# 1-Schematic_TT2.net
KiCad netlist of a schematic drawn in EasyEDA
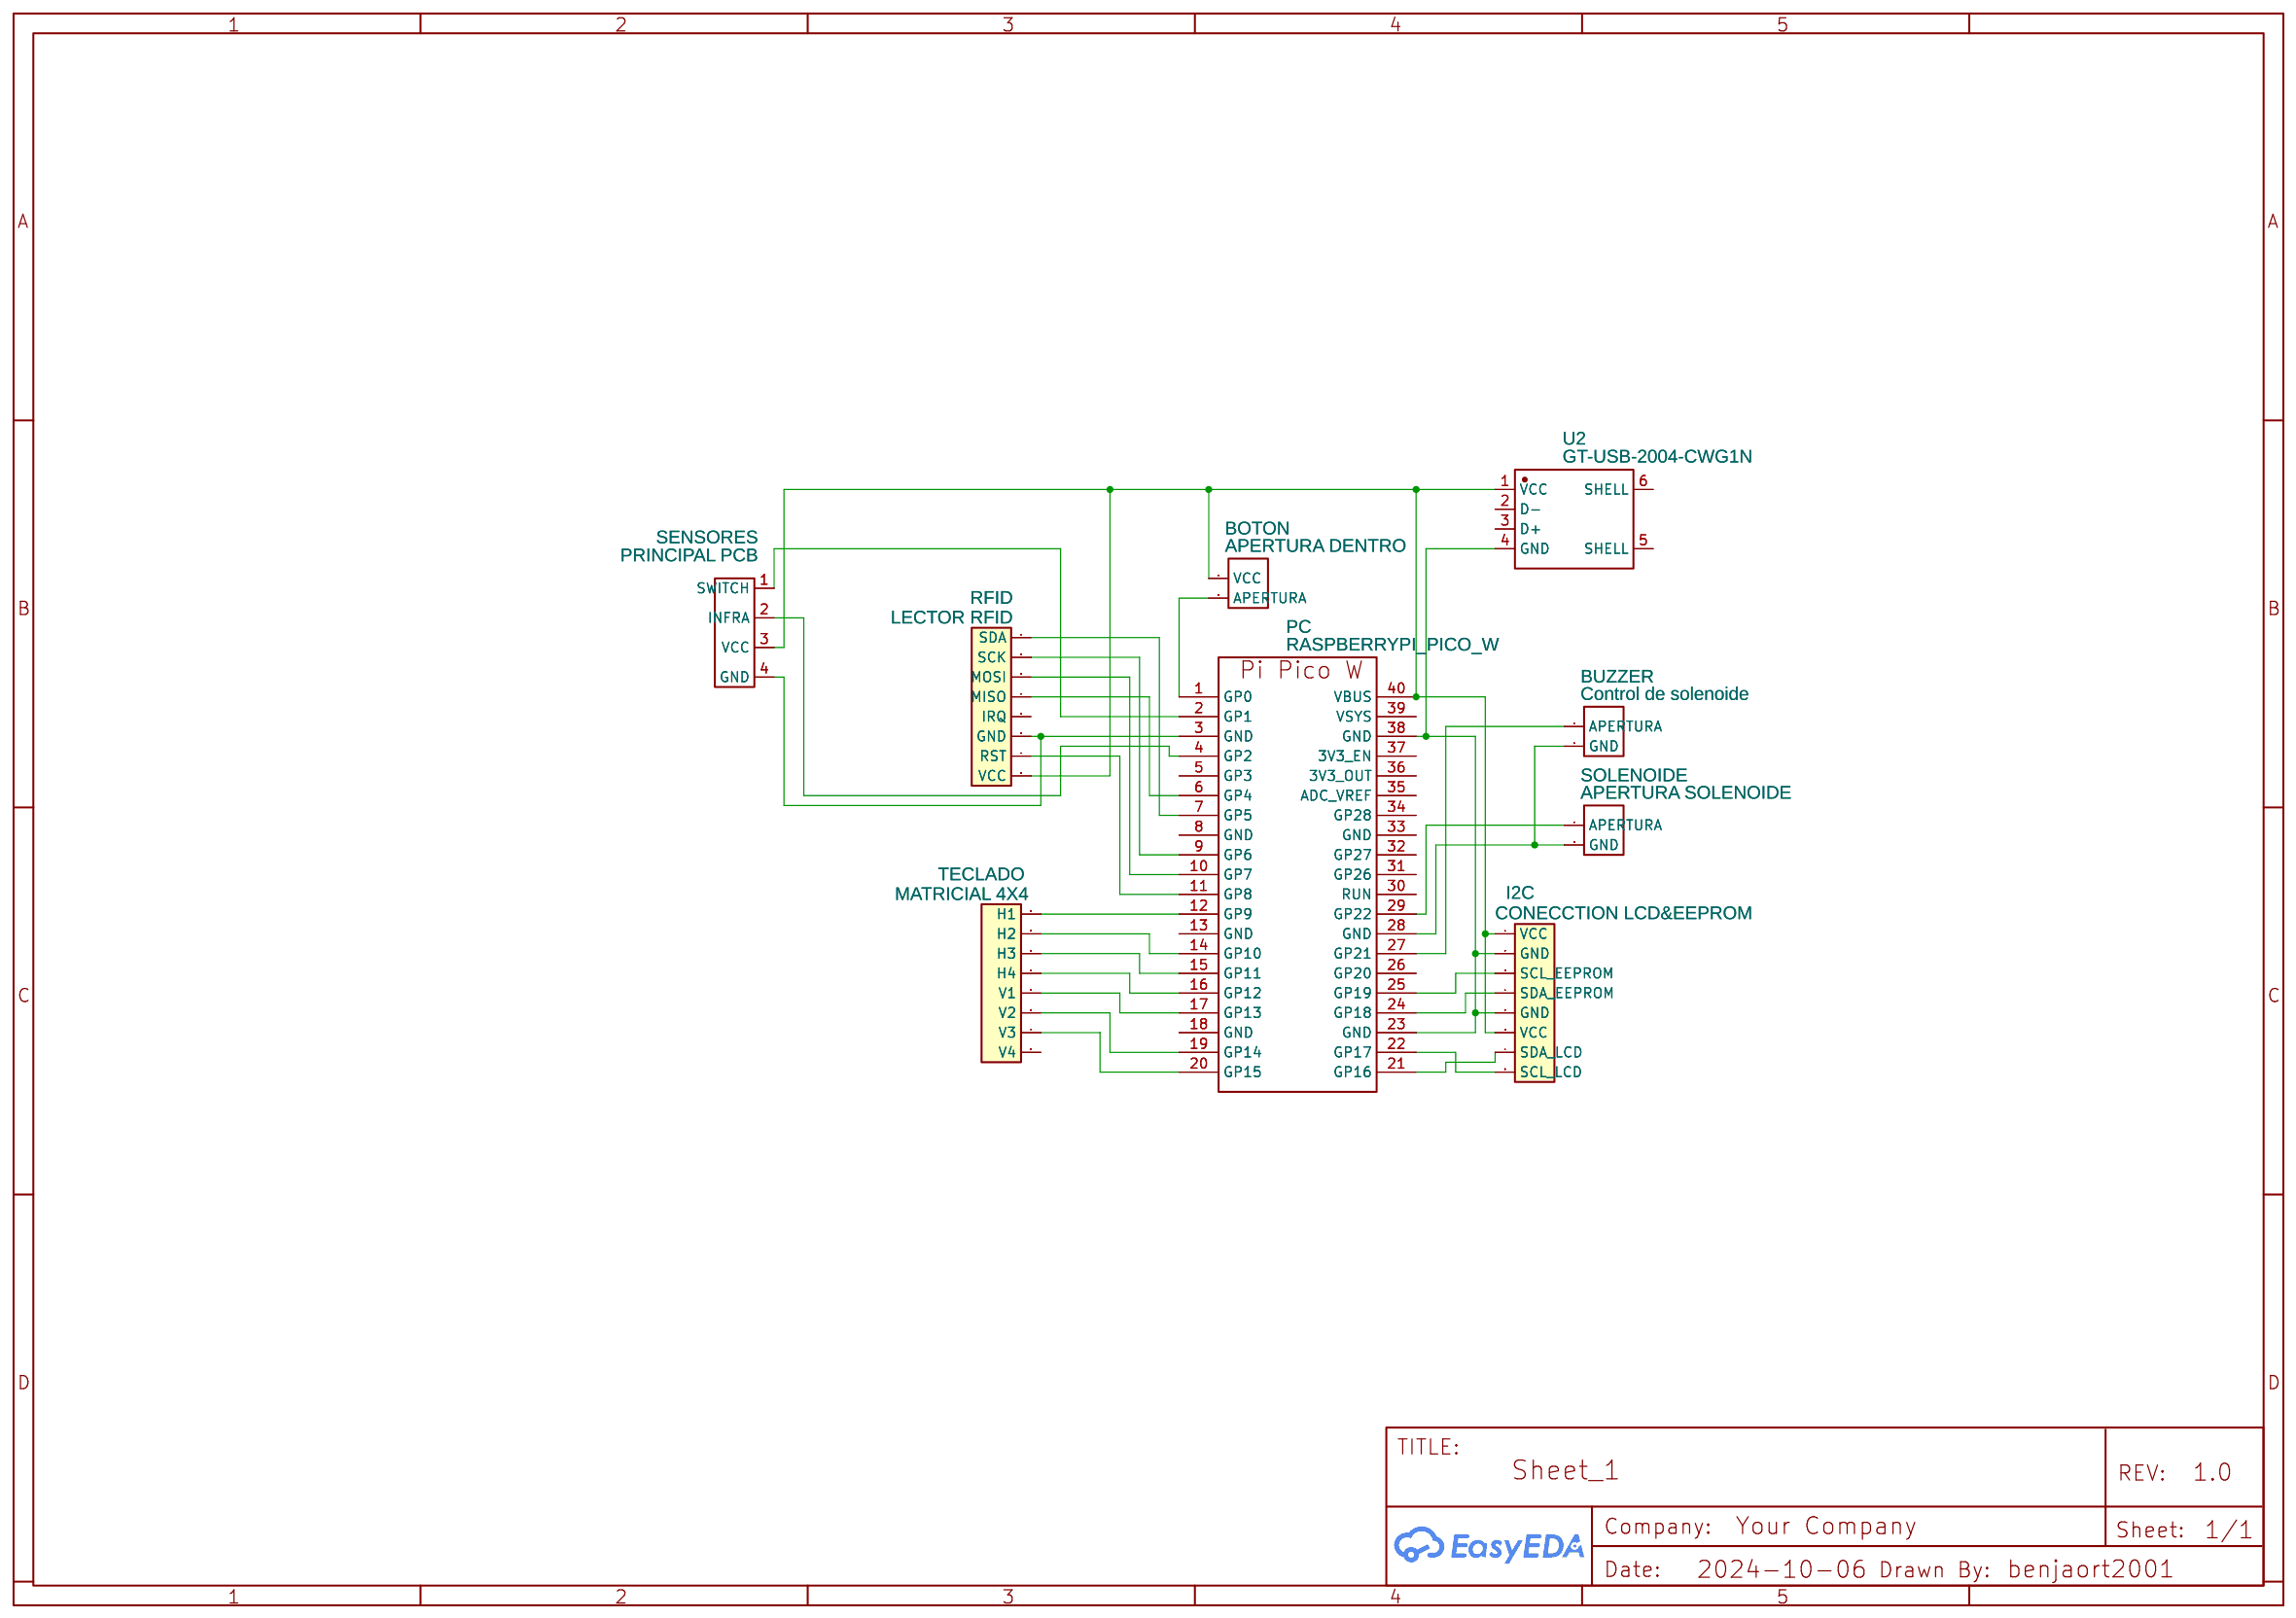
[diagram p0: Sheet_1]
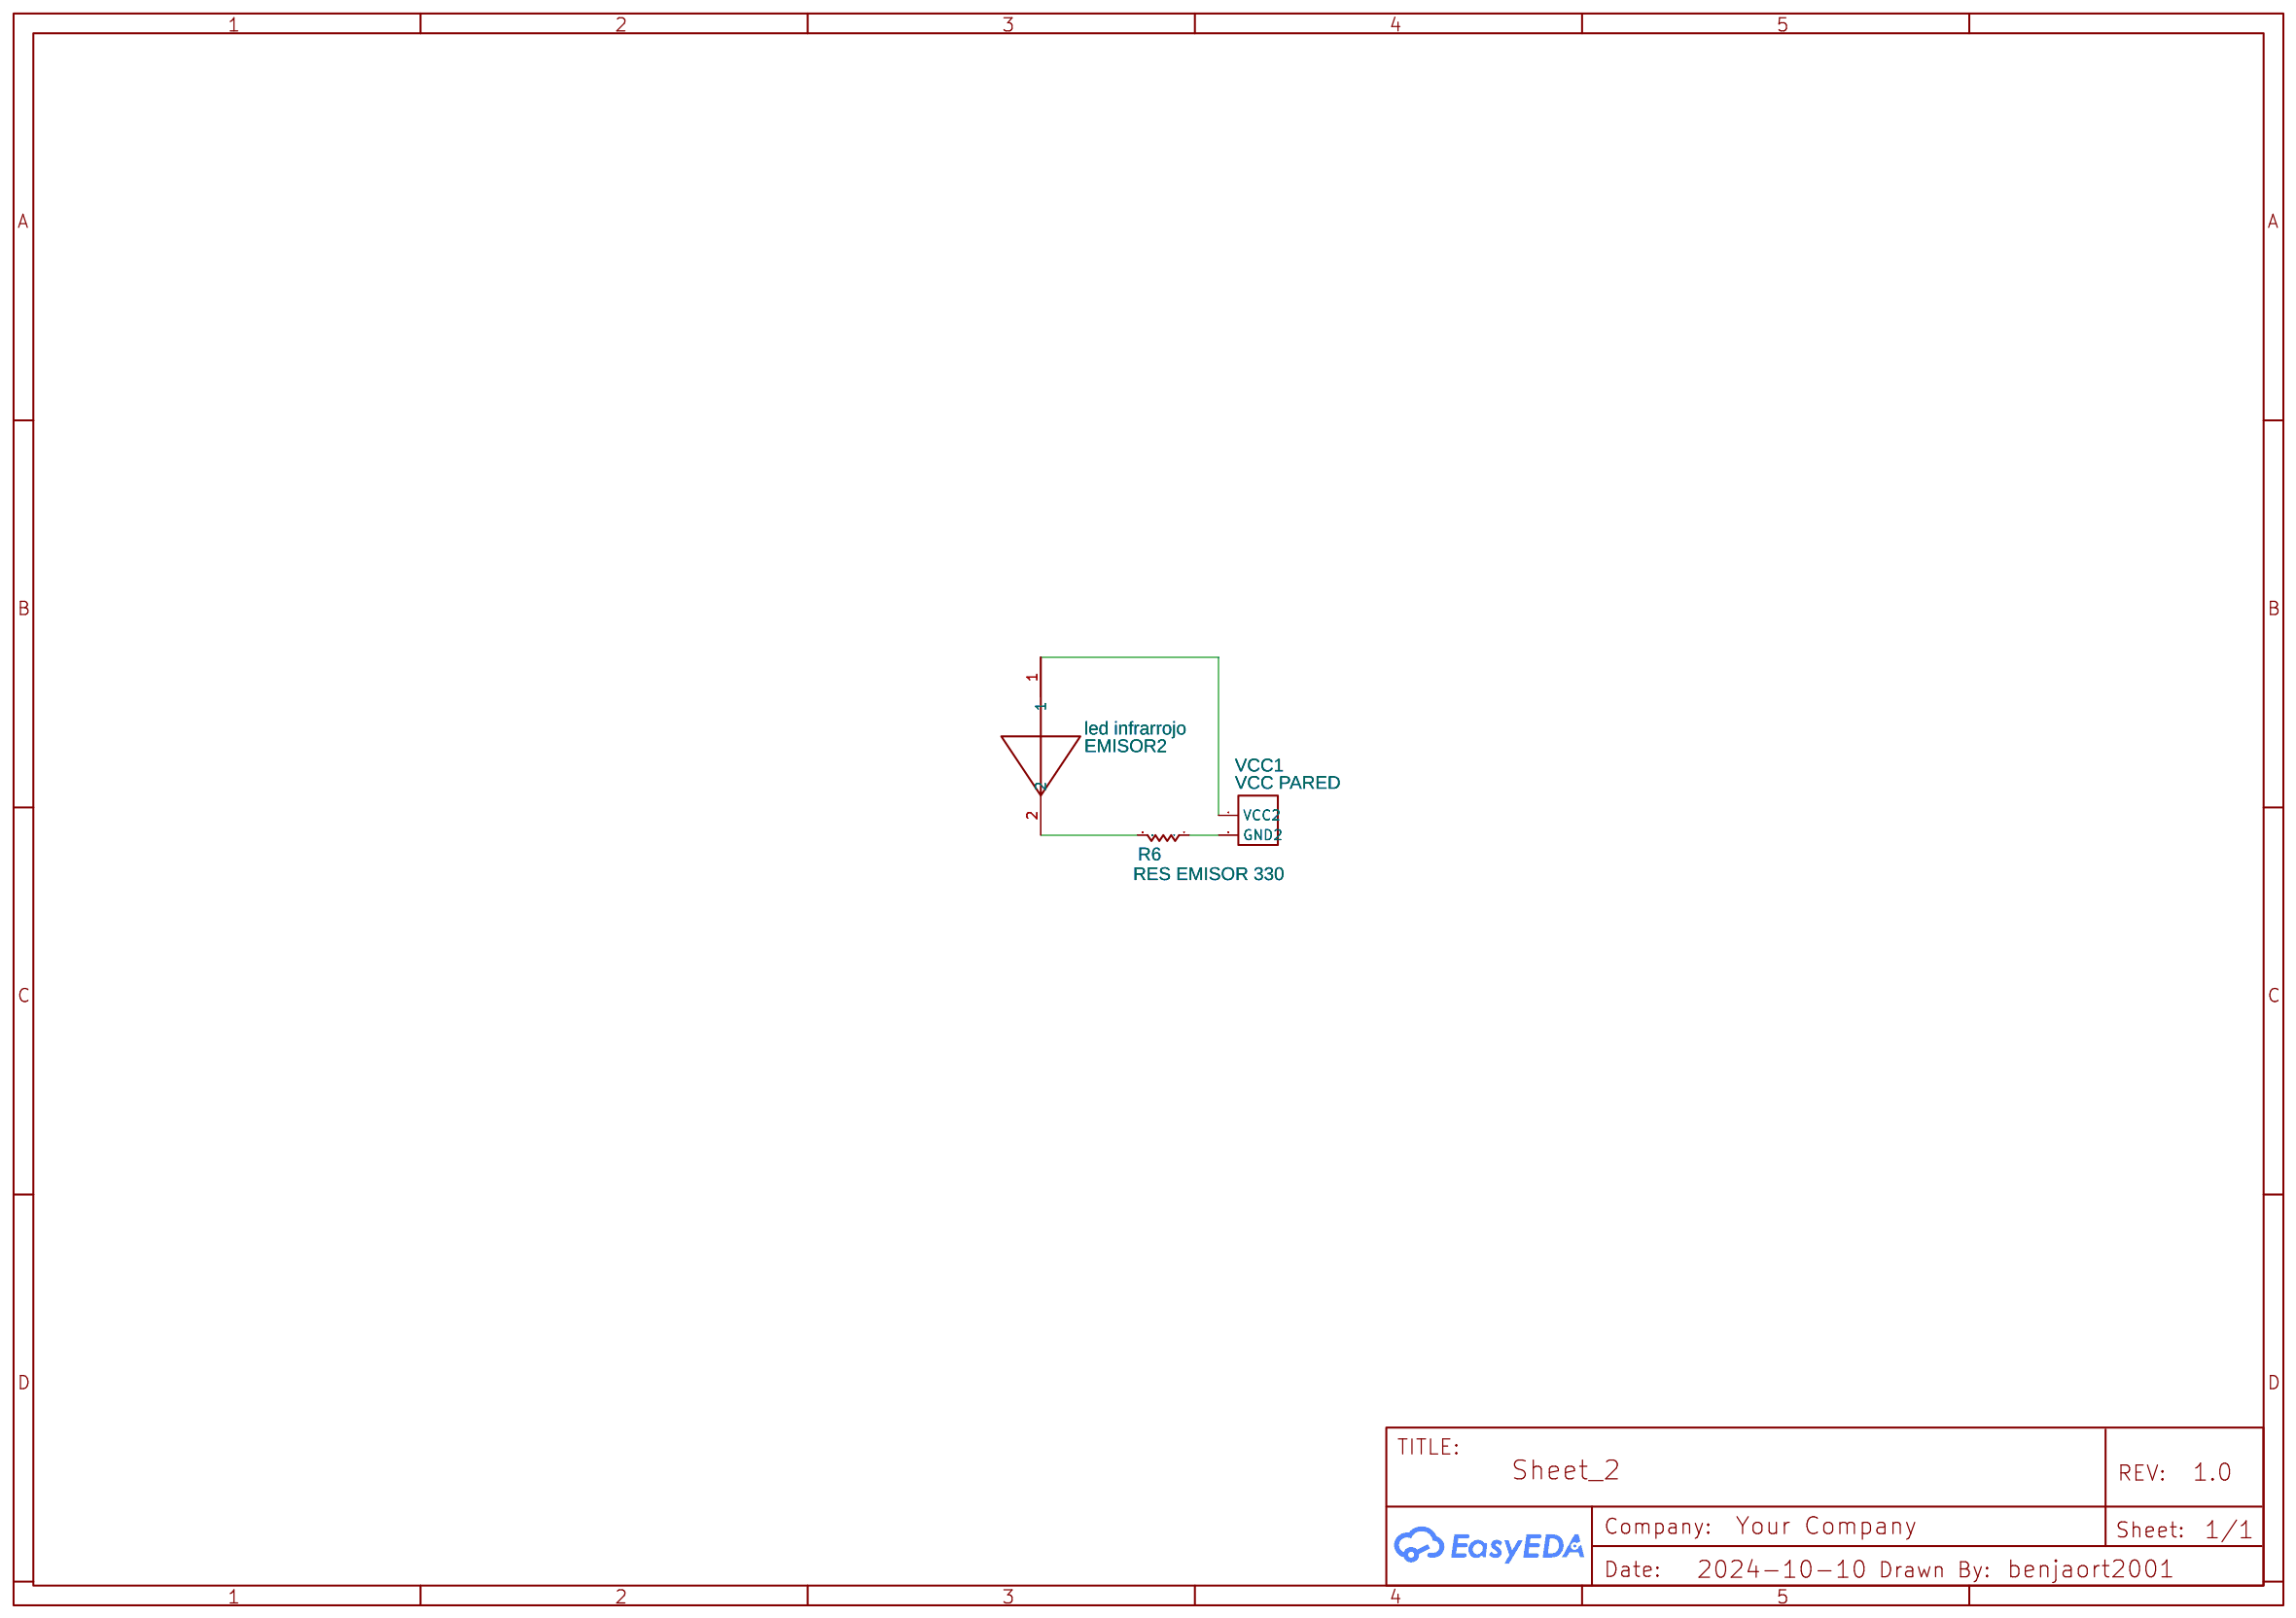
[diagram p1: Sheet_2]
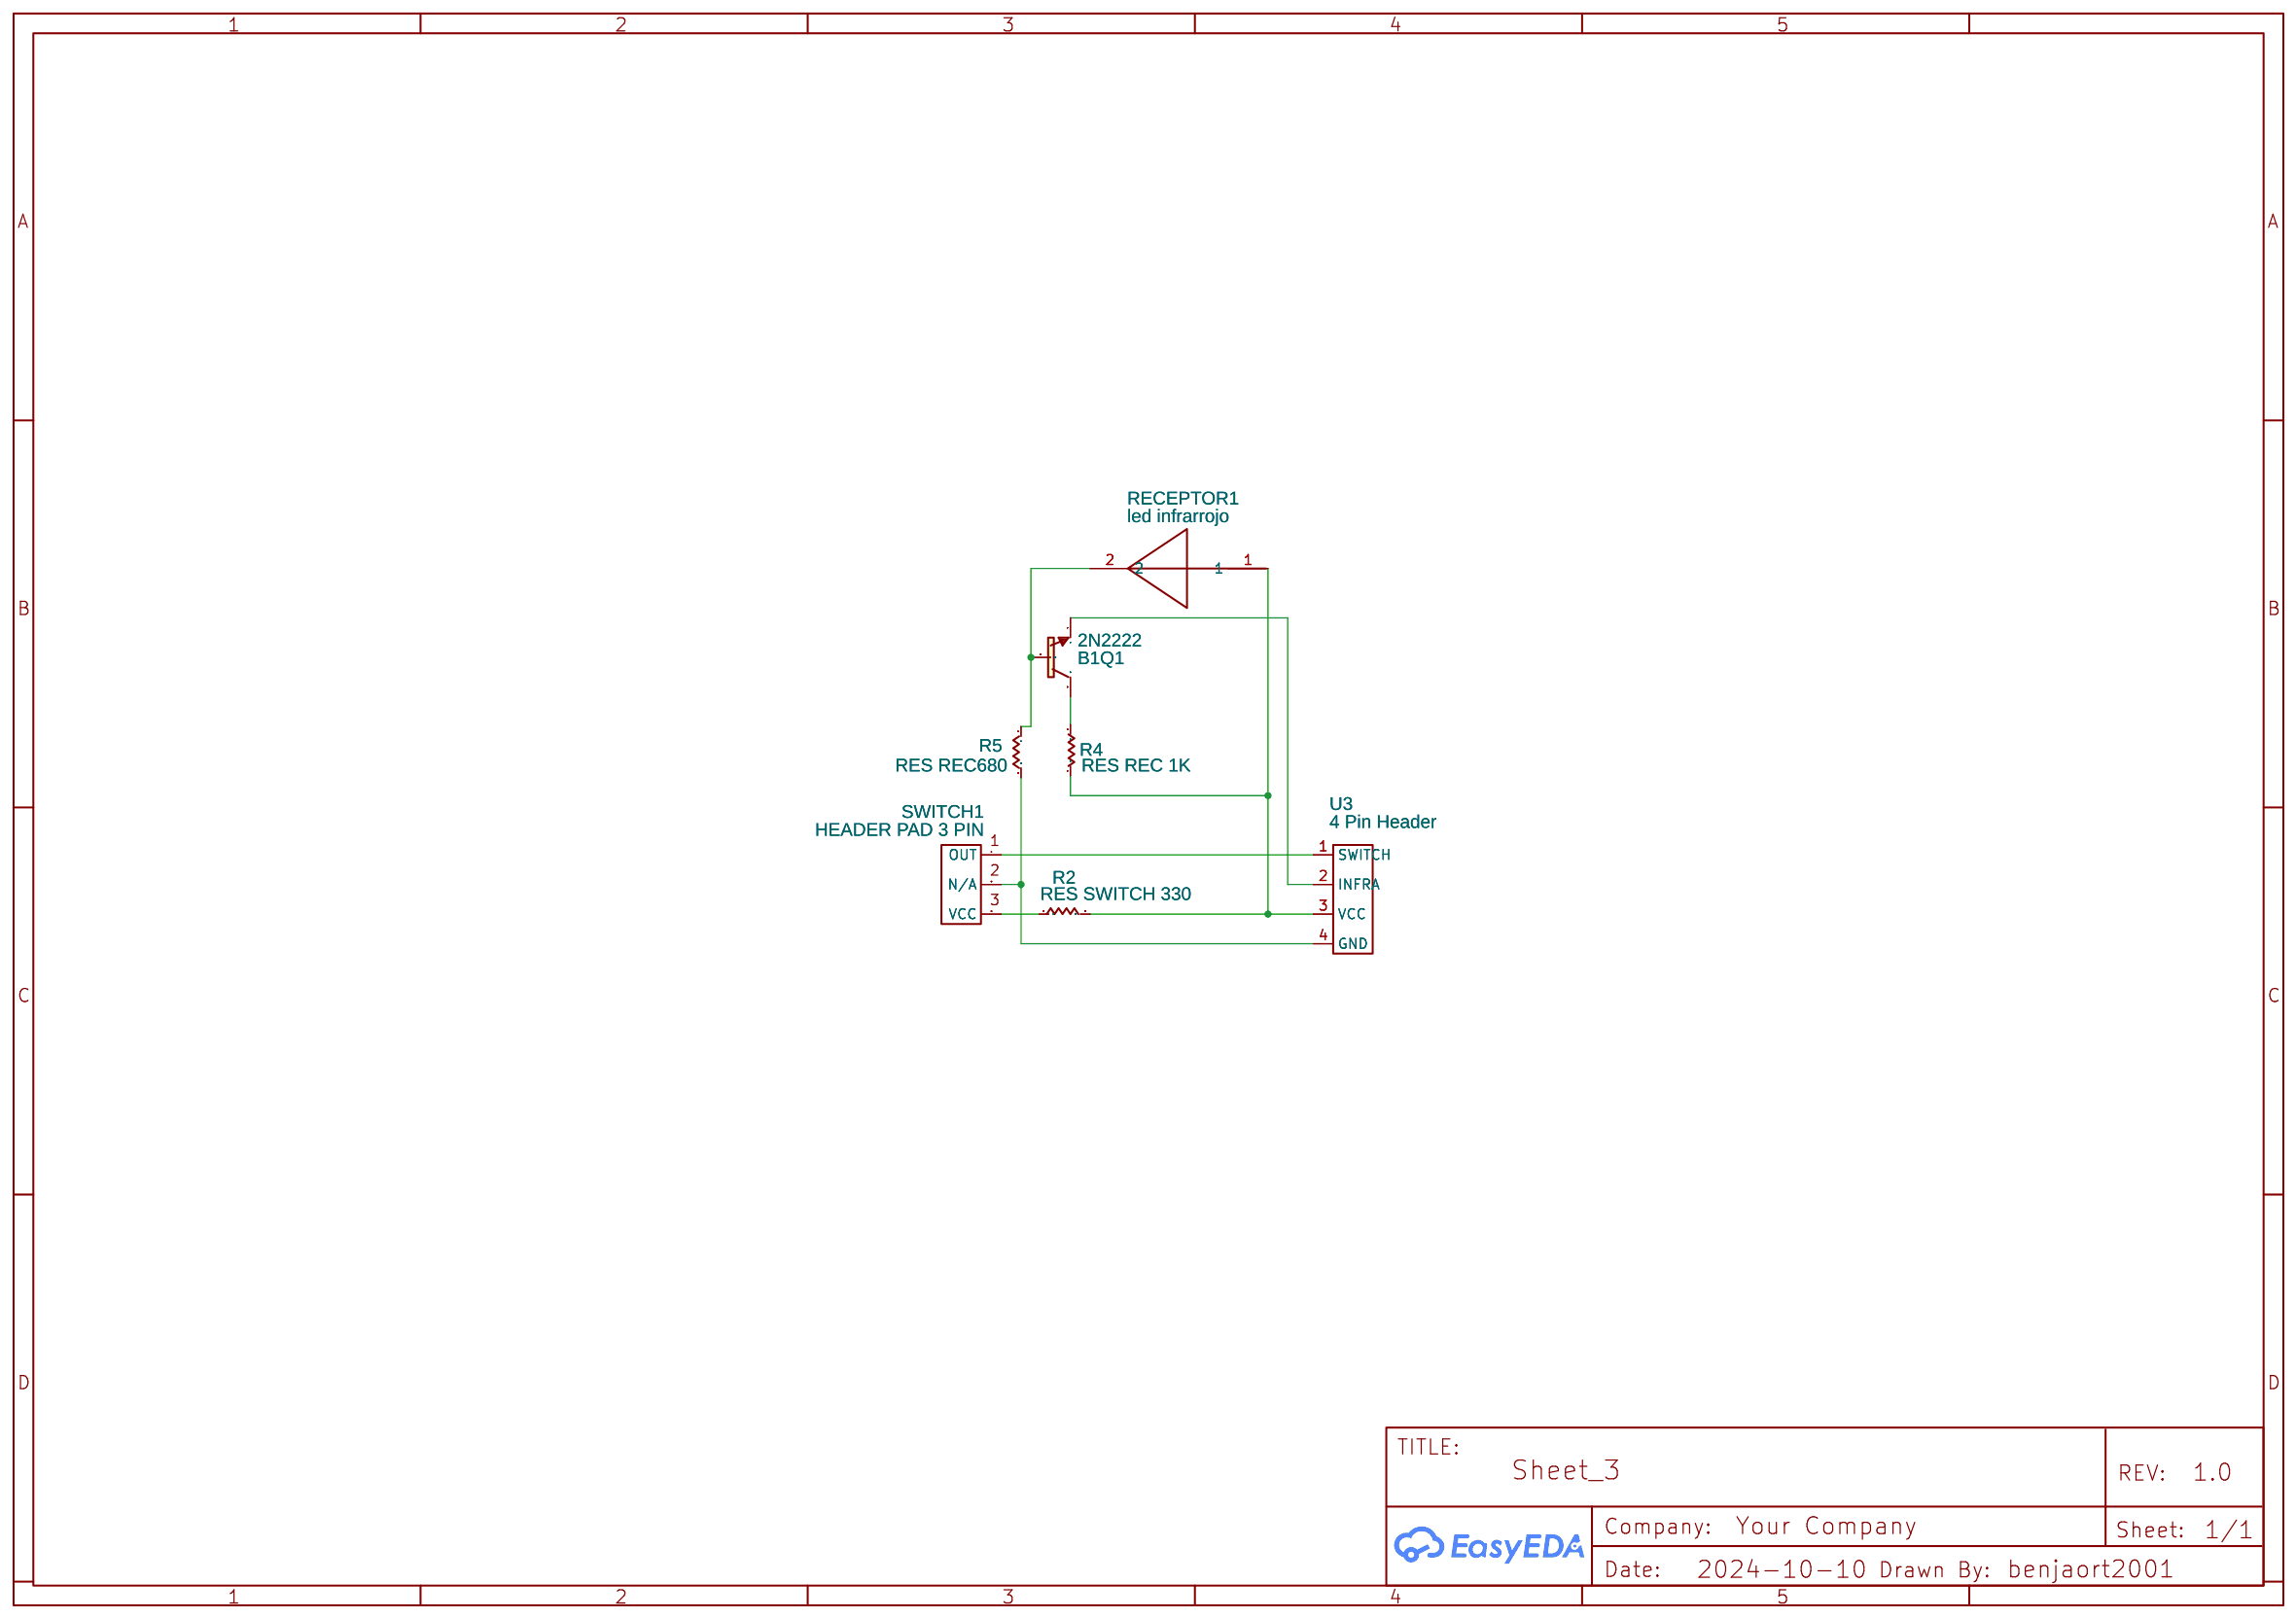
[diagram p2: Sheet_3]

(export (version "E")
  (design (tool "Eeschema 10.0.6"))
  (components
    (comp (ref "BOTON")
      (value "APERTURA DENTRO")
      (fields
        (field (name "Manufacturer Part") "Female headerHDR1X8-2.54")
        (field (name "Manufacturer") "BOOMELE")
      )
      (libsource (lib "") (part "HEADER-FEMALE-2.54_1X2_1"))
    )
    (comp (ref "BUZZER")
      (value "Control de solenoide")
      (fields
        (field (name "Manufacturer Part") "Female headerHDR1X8-2.54")
        (field (name "Manufacturer") "BOOMELE")
      )
      (libsource (lib "") (part "HEADER-FEMALE-2.54_1X2_2"))
    )
    (comp (ref "I2C") (value "CONECCTION LCD&EEPROM") (libsource (lib "") (part "Header 08 copy_1")))
    (comp (ref "PC")
      (value "RASPBERRYPI_PICO_W")
      (fields
        (field (name "Manufacturer Part") "Pi Pico")
        (field (name "Manufacturer") "Raspberry Pi Foundation")
      )
      (libsource (lib "") (part "RASPBERRY PI PICO W Programmer"))
    )
    (comp (ref "RFID") (value "LECTOR RFID") (libsource (lib "") (part "Header 08 copy")))
    (comp (ref "SENSORES") (value "PRINCIPAL PCB") (libsource (lib "") (part "4 Pin Header")))
    (comp (ref "SOLENOIDE")
      (value "APERTURA SOLENOIDE")
      (fields
        (field (name "Manufacturer Part") "Female headerHDR1X8-2.54")
        (field (name "Manufacturer") "BOOMELE")
      )
      (libsource (lib "") (part "HEADER-FEMALE-2.54_1X2"))
    )
    (comp (ref "TECLADO") (value "MATRICIAL 4X4") (libsource (lib "") (part "Header 08 copy_2")))
    (comp (ref "U2")
      (value "GT-USB-2004-CWG1N")
      (fields (field (name "Manufacturer") "G-Switch(品赞)"))
      (libsource (lib "") (part "GT-USB-2004-CWG1N"))
    )
    (comp (ref "EMISOR2") (value "led infrarrojo") (libsource (lib "") (part "led infrarrojo")))
    (comp (ref "R6")
      (value "RES EMISOR 330")
      (fields (field (name "Manufacturer Part") "resistence"))
      (libsource (lib "") (part "Resis"))
    )
    (comp (ref "VCC1")
      (value "VCC PARED")
      (fields
        (field (name "Manufacturer Part") "Female headerHDR1X8-2.54")
        (field (name "Manufacturer") "BOOMELE")
      )
      (libsource (lib "") (part "HEADER-FEMALE-2.54_1X2"))
    )
    (comp (ref "B1Q1")
      (value "2N2222")
      (fields (field (name "Manufacturer Part") "2N2222A"))
      (libsource (lib "") (part "2N2222A facile for souder"))
    )
    (comp (ref "R2")
      (value "RES SWITCH 330")
      (fields (field (name "Manufacturer Part") "resistence"))
      (libsource (lib "") (part "Resis"))
    )
    (comp (ref "R4")
      (value "RES REC 1K")
      (fields (field (name "Manufacturer Part") "resistence"))
      (libsource (lib "") (part "Resis_1"))
    )
    (comp (ref "R5")
      (value "RES REC680")
      (fields (field (name "Manufacturer Part") "resistence"))
      (libsource (lib "") (part "Resis_2"))
    )
    (comp (ref "RECEPTOR1") (value "led infrarrojo") (libsource (lib "") (part "led infrarrojo")))
    (comp (ref "SWITCH1")
      (value "HEADER PAD 3 PIN")
      (fields
        (field (name "Manufacturer Part") "Female headerHDR1X8-2.54")
        (field (name "Manufacturer") "BOOMELE")
      )
      (libsource (lib "") (part "HEADER PAD 3 PIN"))
    )
    (comp (ref "U3") (value "4 Pin Header") (libsource (lib "") (part "4 Pin Header")))
  )
  (nets
    (net (code "1") (name "Net-(B1Q1-B)") (class "Default")
      (node (ref "B1Q1") (pin "2") (pinfunction "B_2") (pintype "unspecified"))
      (node (ref "R5") (pin "1") (pinfunction "1_1") (pintype "unspecified"))
      (node (ref "RECEPTOR1") (pin "2") (pinfunction "2_2") (pintype "unspecified"))
    )
    (net (code "2") (name "Net-(B1Q1-C)") (class "Default")
      (node (ref "B1Q1") (pin "3") (pinfunction "C_3") (pintype "unspecified"))
      (node (ref "R4") (pin "2") (pinfunction "2_2") (pintype "unspecified"))
    )
    (net (code "3") (name "Net-(B1Q1-E)") (class "Default")
      (node (ref "B1Q1") (pin "1") (pinfunction "E_1") (pintype "unspecified"))
      (node (ref "U3") (pin "2") (pinfunction "INFRA_2") (pintype "unspecified"))
    )
    (net (code "4") (name "Net-(BOTON-APERTURA)") (class "Default")
      (node (ref "BOTON") (pin "2") (pinfunction "APERTURA_2") (pintype "input"))
      (node (ref "PC") (pin "1") (pinfunction "GP0_1") (pintype "unspecified"))
    )
    (net (code "5") (name "Net-(BOTON-VCC)") (class "Default")
      (node (ref "BOTON") (pin "1") (pinfunction "VCC_1") (pintype "input"))
      (node (ref "I2C") (pin "1") (pinfunction "VCC_1") (pintype "unspecified"))
      (node (ref "I2C") (pin "6") (pinfunction "VCC_6") (pintype "unspecified"))
      (node (ref "PC") (pin "40") (pinfunction "VBUS_40") (pintype "unspecified"))
      (node (ref "RFID") (pin "8") (pinfunction "VCC_8") (pintype "unspecified"))
      (node (ref "SENSORES") (pin "3") (pinfunction "VCC_3") (pintype "unspecified"))
      (node (ref "U2") (pin "1") (pinfunction "VCC_1") (pintype "unspecified"))
    )
    (net (code "6") (name "Net-(BUZZER-APERTURA)") (class "Default")
      (node (ref "BUZZER") (pin "1") (pinfunction "APERTURA_1") (pintype "input"))
      (node (ref "PC") (pin "27") (pinfunction "GP21_27") (pintype "unspecified"))
    )
    (net (code "7") (name "Net-(BUZZER-GND)") (class "Default")
      (node (ref "BUZZER") (pin "2") (pinfunction "GND_2") (pintype "input"))
      (node (ref "PC") (pin "28") (pinfunction "GND_28") (pintype "unspecified"))
      (node (ref "SOLENOIDE") (pin "2") (pinfunction "GND_2") (pintype "input"))
    )
    (net (code "8") (name "Net-(EMISOR2-Pad2)") (class "Default")
      (node (ref "EMISOR2") (pin "2") (pinfunction "2_2") (pintype "unspecified"))
      (node (ref "R6") (pin "2") (pinfunction "2_2") (pintype "unspecified"))
    )
    (net (code "9") (name "Net-(I2C-SCL_EEPROM)") (class "Default")
      (node (ref "I2C") (pin "3") (pinfunction "SCL_EEPROM_3") (pintype "unspecified"))
      (node (ref "PC") (pin "25") (pinfunction "GP19_25") (pintype "unspecified"))
    )
    (net (code "10") (name "Net-(I2C-SCL_LCD)") (class "Default")
      (node (ref "I2C") (pin "8") (pinfunction "SCL_LCD_8") (pintype "unspecified"))
      (node (ref "PC") (pin "22") (pinfunction "GP17_22") (pintype "unspecified"))
    )
    (net (code "11") (name "Net-(I2C-SDA_EEPROM)") (class "Default")
      (node (ref "I2C") (pin "4") (pinfunction "SDA_EEPROM_4") (pintype "unspecified"))
      (node (ref "PC") (pin "24") (pinfunction "GP18_24") (pintype "unspecified"))
    )
    (net (code "12") (name "Net-(I2C-SDA_LCD)") (class "Default")
      (node (ref "I2C") (pin "7") (pinfunction "SDA_LCD_7") (pintype "unspecified"))
      (node (ref "PC") (pin "21") (pinfunction "GP16_21") (pintype "unspecified"))
    )
    (net (code "13") (name "Net-(PC-GP1)") (class "Default")
      (node (ref "PC") (pin "2") (pinfunction "GP1_2") (pintype "unspecified"))
      (node (ref "SENSORES") (pin "1") (pinfunction "SWITCH_1") (pintype "unspecified"))
    )
    (net (code "14") (name "Net-(PC-GP2)") (class "Default")
      (node (ref "PC") (pin "4") (pinfunction "GP2_4") (pintype "unspecified"))
      (node (ref "SENSORES") (pin "2") (pinfunction "INFRA_2") (pintype "unspecified"))
    )
    (net (code "15") (name "Net-(PC-GP4)") (class "Default")
      (node (ref "PC") (pin "6") (pinfunction "GP4_6") (pintype "unspecified"))
      (node (ref "RFID") (pin "4") (pinfunction "MISO_4") (pintype "unspecified"))
    )
    (net (code "16") (name "Net-(PC-GP5)") (class "Default")
      (node (ref "PC") (pin "7") (pinfunction "GP5_7") (pintype "unspecified"))
      (node (ref "RFID") (pin "1") (pinfunction "SDA_1") (pintype "unspecified"))
    )
    (net (code "17") (name "Net-(PC-GP6)") (class "Default")
      (node (ref "PC") (pin "9") (pinfunction "GP6_9") (pintype "unspecified"))
      (node (ref "RFID") (pin "2") (pinfunction "SCK_2") (pintype "unspecified"))
    )
    (net (code "18") (name "Net-(PC-GP7)") (class "Default")
      (node (ref "PC") (pin "10") (pinfunction "GP7_10") (pintype "unspecified"))
      (node (ref "RFID") (pin "3") (pinfunction "MOSI_3") (pintype "unspecified"))
    )
    (net (code "19") (name "Net-(PC-GP8)") (class "Default")
      (node (ref "PC") (pin "11") (pinfunction "GP8_11") (pintype "unspecified"))
      (node (ref "RFID") (pin "7") (pinfunction "RST_7") (pintype "unspecified"))
    )
    (net (code "20") (name "Net-(PC-GP9)") (class "Default")
      (node (ref "PC") (pin "12") (pinfunction "GP9_12") (pintype "unspecified"))
      (node (ref "TECLADO") (pin "1") (pinfunction "H1_1") (pintype "unspecified"))
    )
    (net (code "21") (name "Net-(PC-GP10)") (class "Default")
      (node (ref "PC") (pin "14") (pinfunction "GP10_14") (pintype "unspecified"))
      (node (ref "TECLADO") (pin "2") (pinfunction "H2_2") (pintype "unspecified"))
    )
    (net (code "22") (name "Net-(PC-GP11)") (class "Default")
      (node (ref "PC") (pin "15") (pinfunction "GP11_15") (pintype "unspecified"))
      (node (ref "TECLADO") (pin "3") (pinfunction "H3_3") (pintype "unspecified"))
    )
    (net (code "23") (name "Net-(PC-GP12)") (class "Default")
      (node (ref "PC") (pin "16") (pinfunction "GP12_16") (pintype "unspecified"))
      (node (ref "TECLADO") (pin "4") (pinfunction "H4_4") (pintype "unspecified"))
    )
    (net (code "24") (name "Net-(PC-GP13)") (class "Default")
      (node (ref "PC") (pin "17") (pinfunction "GP13_17") (pintype "unspecified"))
      (node (ref "TECLADO") (pin "5") (pinfunction "V1_5") (pintype "unspecified"))
    )
    (net (code "25") (name "Net-(PC-GP14)") (class "Default")
      (node (ref "PC") (pin "19") (pinfunction "GP14_19") (pintype "unspecified"))
      (node (ref "TECLADO") (pin "6") (pinfunction "V2_6") (pintype "unspecified"))
    )
    (net (code "26") (name "Net-(PC-GP15)") (class "Default")
      (node (ref "PC") (pin "20") (pinfunction "GP15_20") (pintype "unspecified"))
      (node (ref "TECLADO") (pin "7") (pinfunction "V3_7") (pintype "unspecified"))
    )
    (net (code "27") (name "Net-(PC-GP22)") (class "Default")
      (node (ref "PC") (pin "29") (pinfunction "GP22_29") (pintype "unspecified"))
      (node (ref "SOLENOIDE") (pin "1") (pinfunction "APERTURA_1") (pintype "input"))
    )
    (net (code "28") (name "Net-(RFID-GND)") (class "Default")
      (node (ref "PC") (pin "3") (pinfunction "GND_3") (pintype "unspecified"))
      (node (ref "RFID") (pin "6") (pinfunction "GND_6") (pintype "unspecified"))
      (node (ref "SENSORES") (pin "4") (pinfunction "GND_4") (pintype "unspecified"))
    )
    (net (code "29") (name "Net-(SWITCH1-N{slash}A)") (class "Default")
      (node (ref "R5") (pin "2") (pinfunction "2_2") (pintype "unspecified"))
      (node (ref "SWITCH1") (pin "2") (pinfunction "N/A_2") (pintype "input"))
      (node (ref "U3") (pin "4") (pinfunction "GND_4") (pintype "unspecified"))
    )
    (net (code "30") (name "Net-(SWITCH1-OUT)") (class "Default")
      (node (ref "SWITCH1") (pin "1") (pinfunction "OUT_1") (pintype "input"))
      (node (ref "U3") (pin "1") (pinfunction "SWITCH_1") (pintype "unspecified"))
    )
    (net (code "31") (name "Net-(SWITCH1-VCC)") (class "Default")
      (node (ref "R2") (pin "2") (pinfunction "2_2") (pintype "unspecified"))
      (node (ref "SWITCH1") (pin "3") (pinfunction "VCC_3") (pintype "input"))
    )
    (net (code "32") (name "Net-(U2-GND)") (class "Default")
      (node (ref "I2C") (pin "2") (pinfunction "GND_2") (pintype "unspecified"))
      (node (ref "I2C") (pin "5") (pinfunction "GND_5") (pintype "unspecified"))
      (node (ref "PC") (pin "23") (pinfunction "GND_23") (pintype "unspecified"))
      (node (ref "PC") (pin "38") (pinfunction "GND_38") (pintype "unspecified"))
      (node (ref "U2") (pin "4") (pinfunction "GND_4") (pintype "unspecified"))
    )
    (net (code "33") (name "Net-(U3-VCC)") (class "Default")
      (node (ref "R2") (pin "1") (pinfunction "1_1") (pintype "unspecified"))
      (node (ref "R4") (pin "1") (pinfunction "1_1") (pintype "unspecified"))
      (node (ref "RECEPTOR1") (pin "1") (pinfunction "1_1") (pintype "unspecified"))
      (node (ref "U3") (pin "3") (pinfunction "VCC_3") (pintype "unspecified"))
    )
    (net (code "34") (name "Net-(VCC1-GND2)") (class "Default")
      (node (ref "R6") (pin "1") (pinfunction "1_1") (pintype "unspecified"))
      (node (ref "VCC1") (pin "2") (pinfunction "GND2_2") (pintype "input"))
    )
    (net (code "35") (name "Net-(VCC1-VCC2)") (class "Default")
      (node (ref "EMISOR2") (pin "1") (pinfunction "1_1") (pintype "unspecified"))
      (node (ref "VCC1") (pin "1") (pinfunction "VCC2_1") (pintype "input"))
    )
    (net (code "36") (name "unconnected-(PC-3V3_EN-Pad37)") (class "Default")
      (node (ref "PC") (pin "37") (pinfunction "3V3_EN_37") (pintype "unspecified"))
    )
    (net (code "37") (name "unconnected-(PC-3V3_OUT-Pad36)") (class "Default")
      (node (ref "PC") (pin "36") (pinfunction "3V3_OUT_36") (pintype "unspecified"))
    )
    (net (code "38") (name "unconnected-(PC-ADC_VREF-Pad35)") (class "Default")
      (node (ref "PC") (pin "35") (pinfunction "ADC_VREF_35") (pintype "unspecified"))
    )
    (net (code "39") (name "unconnected-(PC-GND-Pad8)") (class "Default")
      (node (ref "PC") (pin "8") (pinfunction "GND_8") (pintype "unspecified"))
    )
    (net (code "40") (name "unconnected-(PC-GND-Pad13)") (class "Default")
      (node (ref "PC") (pin "13") (pinfunction "GND_13") (pintype "unspecified"))
    )
    (net (code "41") (name "unconnected-(PC-GND-Pad18)") (class "Default")
      (node (ref "PC") (pin "18") (pinfunction "GND_18") (pintype "unspecified"))
    )
    (net (code "42") (name "unconnected-(PC-GND-Pad33)") (class "Default")
      (node (ref "PC") (pin "33") (pinfunction "GND_33") (pintype "unspecified"))
    )
    (net (code "43") (name "unconnected-(PC-GP3-Pad5)") (class "Default")
      (node (ref "PC") (pin "5") (pinfunction "GP3_5") (pintype "unspecified"))
    )
    (net (code "44") (name "unconnected-(PC-GP20-Pad26)") (class "Default")
      (node (ref "PC") (pin "26") (pinfunction "GP20_26") (pintype "unspecified"))
    )
    (net (code "45") (name "unconnected-(PC-GP26-Pad31)") (class "Default")
      (node (ref "PC") (pin "31") (pinfunction "GP26_31") (pintype "unspecified"))
    )
    (net (code "46") (name "unconnected-(PC-GP27-Pad32)") (class "Default")
      (node (ref "PC") (pin "32") (pinfunction "GP27_32") (pintype "unspecified"))
    )
    (net (code "47") (name "unconnected-(PC-GP28-Pad34)") (class "Default")
      (node (ref "PC") (pin "34") (pinfunction "GP28_34") (pintype "unspecified"))
    )
    (net (code "48") (name "unconnected-(PC-RUN-Pad30)") (class "Default")
      (node (ref "PC") (pin "30") (pinfunction "RUN_30") (pintype "unspecified"))
    )
    (net (code "49") (name "unconnected-(PC-VSYS-Pad39)") (class "Default")
      (node (ref "PC") (pin "39") (pinfunction "VSYS_39") (pintype "unspecified"))
    )
    (net (code "50") (name "unconnected-(RFID-IRQ-Pad5)") (class "Default")
      (node (ref "RFID") (pin "5") (pinfunction "IRQ_5") (pintype "unspecified"))
    )
    (net (code "51") (name "unconnected-(TECLADO-V4-Pad8)") (class "Default")
      (node (ref "TECLADO") (pin "8") (pinfunction "V4_8") (pintype "unspecified"))
    )
    (net (code "52") (name "unconnected-(U2-D+-Pad3)") (class "Default")
      (node (ref "U2") (pin "3") (pinfunction "D+_3") (pintype "unspecified"))
    )
    (net (code "53") (name "unconnected-(U2-D--Pad2)") (class "Default")
      (node (ref "U2") (pin "2") (pinfunction "D-_2") (pintype "unspecified"))
    )
    (net (code "54") (name "unconnected-(U2-SHELL-Pad5)") (class "Default")
      (node (ref "U2") (pin "5") (pinfunction "SHELL_5") (pintype "unspecified"))
    )
    (net (code "55") (name "unconnected-(U2-SHELL-Pad6)") (class "Default")
      (node (ref "U2") (pin "6") (pinfunction "SHELL_6") (pintype "unspecified"))
    )
  )
)
